# Power_Sense_Rev_2_2_1.net
KiCad netlist of a schematic drawn in EAGLE
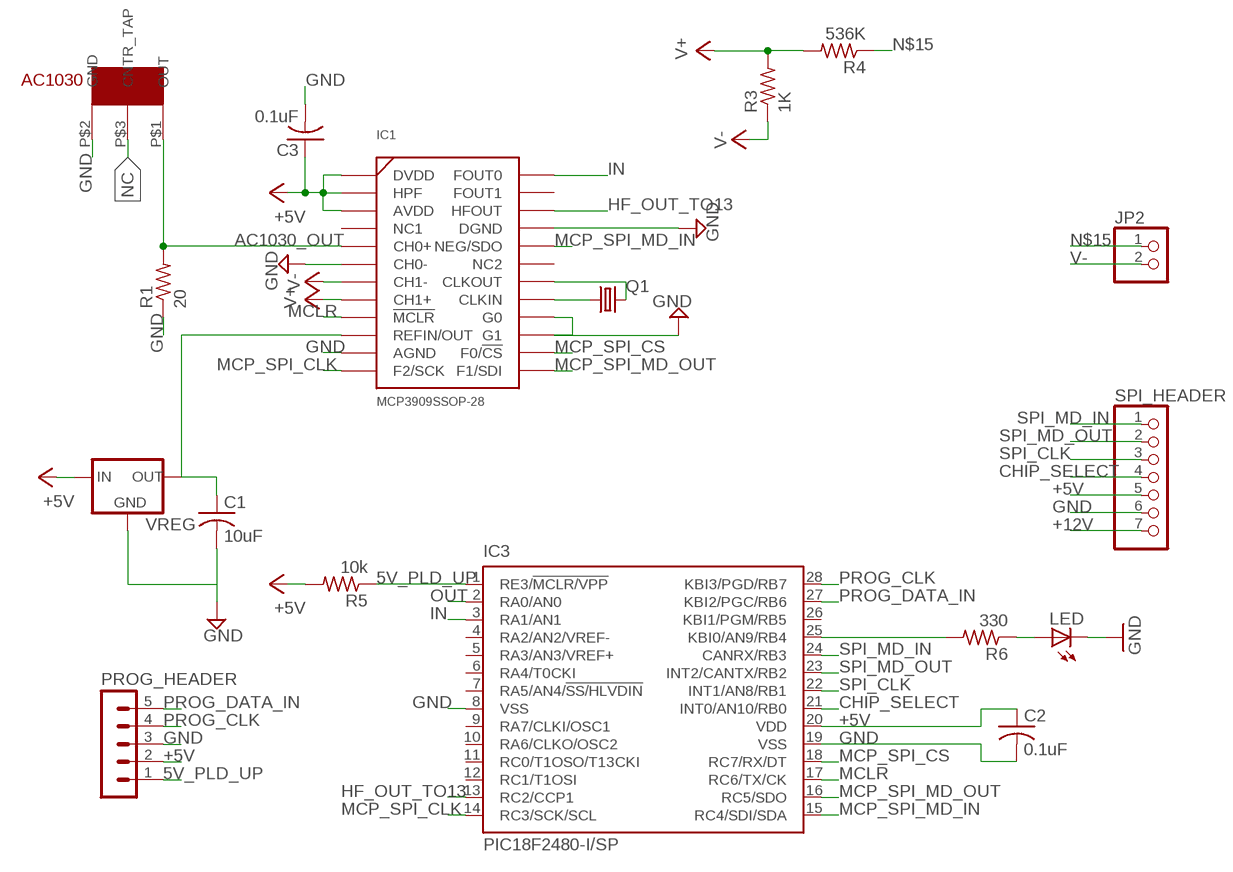
[diagram p0: schematic, sheet 1]

(export (version "E")
  (design (tool "Eeschema 10.0.6"))
  (components
    (comp (ref "AC1030")
      (value "AC1030")
      (footprint "eagle-import:AC1030")
      (libsource (lib "eagle-import") (part "AC1030"))
    )
    (comp (ref "C1")
      (value "10uF")
      (footprint "eagle-import:C025-024X044")
      (libsource (lib "eagle-import") (part "C-US025-024X044"))
    )
    (comp (ref "C2")
      (value "0.1uF")
      (footprint "eagle-import:C025-024X044")
      (libsource (lib "eagle-import") (part "C-US025-024X044"))
    )
    (comp (ref "C3")
      (value "0.1uF")
      (footprint "eagle-import:C025-024X044")
      (libsource (lib "eagle-import") (part "C-US025-024X044"))
    )
    (comp (ref "IC1")
      (value "MCP3909SSOP-28")
      (footprint "eagle-import:SSOP-24")
      (libsource (lib "eagle-import") (part "MCP3909SSOP-28"))
    )
    (comp (ref "IC3")
      (value "PIC18F2480-I/SP")
      (footprint "eagle-import:DIL28-3")
      (fields (field (name "MF") "MICROCHIP"))
      (libsource (lib "eagle-import") (part "PIC18F280-I/SP4"))
    )
    (comp (ref "JP2")
      (value "PINHD-1X2")
      (footprint "eagle-import:1X02")
      (libsource (lib "eagle-import") (part "PINHD-1X2"))
    )
    (comp (ref "LED")
      (value "LED3MM")
      (footprint "eagle-import:LED3MM")
      (libsource (lib "eagle-import") (part "LED3MM"))
    )
    (comp (ref "PROG_HEADER")
      (value "MA05-1")
      (footprint "eagle-import:MA05-1")
      (libsource (lib "eagle-import") (part "MA05-1"))
    )
    (comp (ref "Q1")
      (value "CRYSTALHC49S")
      (footprint "eagle-import:HC49_S")
      (libsource (lib "eagle-import") (part "CRYSTALHC49S"))
    )
    (comp (ref "R1")
      (value "20")
      (footprint "eagle-import:0204_7")
      (libsource (lib "eagle-import") (part "R-US_0204/7"))
    )
    (comp (ref "R3")
      (value "1K")
      (footprint "eagle-import:0204_7")
      (libsource (lib "eagle-import") (part "R-US_0204/7"))
    )
    (comp (ref "R4")
      (value "536K")
      (footprint "eagle-import:0204_7")
      (libsource (lib "eagle-import") (part "R-US_0204/7"))
    )
    (comp (ref "R5")
      (value "10k")
      (footprint "eagle-import:0204_7")
      (libsource (lib "eagle-import") (part "R-US_0204/7"))
    )
    (comp (ref "R6")
      (value "330")
      (footprint "eagle-import:0204_7")
      (libsource (lib "eagle-import") (part "R-US_0204/7"))
    )
    (comp (ref "SPI_HEADER")
      (value "PINHD-1X7")
      (footprint "eagle-import:1X07")
      (libsource (lib "eagle-import") (part "PINHD-1X7"))
    )
    (comp (ref "VREG")
      (value "MCP1700INLINE")
      (footprint "eagle-import:TO92-INLINE")
      (libsource (lib "eagle-import") (part "MCP1700INLINE"))
    )
  )
  (nets
    (net (code "1") (name "+5V") (class "Default")
      (node (ref "C2") (pin "1") (pinfunction "1_1") (pintype "passive"))
      (node (ref "C3") (pin "1") (pinfunction "1_1") (pintype "passive"))
      (node (ref "IC1") (pin "1") (pinfunction "DVDD_1") (pintype "bidirectional"))
      (node (ref "IC1") (pin "2") (pinfunction "HPF_2") (pintype "bidirectional"))
      (node (ref "IC1") (pin "3") (pinfunction "AVDD_3") (pintype "bidirectional"))
      (node (ref "IC3") (pin "20") (pinfunction "VDD_20") (pintype "power_in"))
      (node (ref "PROG_HEADER") (pin "2") (pinfunction "2_2") (pintype "passive"))
      (node (ref "R5") (pin "2") (pinfunction "2_2") (pintype "passive"))
      (node (ref "SPI_HEADER") (pin "5") (pinfunction "5_5") (pintype "passive"))
      (node (ref "VREG") (pin "2") (pinfunction "IN_2") (pintype "input"))
    )
    (net (code "2") (name "/+12V") (class "Default")
      (node (ref "SPI_HEADER") (pin "7") (pinfunction "7_7") (pintype "passive"))
    )
    (net (code "3") (name "/5V_PLD_UP") (class "Default")
      (node (ref "IC3") (pin "1") (pinfunction "RE3/~{MCLR/VPP}_1") (pintype "input"))
      (node (ref "PROG_HEADER") (pin "1") (pinfunction "1_1") (pintype "passive"))
      (node (ref "R5") (pin "1") (pinfunction "1_1") (pintype "passive"))
    )
    (net (code "4") (name "/AC1030_OUT") (class "Default")
      (node (ref "AC1030") (pin "P$1") (pinfunction "OUT_P$1") (pintype "output"))
      (node (ref "IC1") (pin "5") (pinfunction "CH0+_5") (pintype "bidirectional"))
      (node (ref "R1") (pin "2") (pinfunction "2_2") (pintype "passive"))
    )
    (net (code "5") (name "/CHIP_SELECT") (class "Default")
      (node (ref "IC3") (pin "21") (pinfunction "INT0/AN10/RB0_21") (pintype "bidirectional"))
      (node (ref "SPI_HEADER") (pin "4") (pinfunction "4_4") (pintype "passive"))
    )
    (net (code "6") (name "/HF_OUT_TO13") (class "Default")
      (node (ref "IC1") (pin "22") (pinfunction "HFOUT_22") (pintype "bidirectional"))
      (node (ref "IC3") (pin "13") (pinfunction "RC2/CCP1_13") (pintype "bidirectional"))
    )
    (net (code "7") (name "/IN") (class "Default")
      (node (ref "IC1") (pin "24") (pinfunction "FOUT0_24") (pintype "bidirectional"))
      (node (ref "IC3") (pin "3") (pinfunction "RA1/AN1_3") (pintype "bidirectional"))
    )
    (net (code "8") (name "/MCLR") (class "Default")
      (node (ref "IC1") (pin "9") (pinfunction "~{MCLR}_9") (pintype "bidirectional"))
      (node (ref "IC3") (pin "17") (pinfunction "RC6/TX/CK_17") (pintype "bidirectional"))
    )
    (net (code "9") (name "/MCP_SPI_CLK") (class "Default")
      (node (ref "IC1") (pin "12") (pinfunction "F2/SCK_12") (pintype "bidirectional"))
      (node (ref "IC3") (pin "14") (pinfunction "RC3/SCK/SCL_14") (pintype "bidirectional"))
    )
    (net (code "10") (name "/MCP_SPI_CS") (class "Default")
      (node (ref "IC1") (pin "14") (pinfunction "F0/~{CS}_14") (pintype "bidirectional"))
      (node (ref "IC3") (pin "18") (pinfunction "RC7/RX/DT_18") (pintype "bidirectional"))
    )
    (net (code "11") (name "/MCP_SPI_MD_IN") (class "Default")
      (node (ref "IC1") (pin "20") (pinfunction "NEG/SDO_20") (pintype "bidirectional"))
      (node (ref "IC3") (pin "15") (pinfunction "RC4/SDI/SDA_15") (pintype "bidirectional"))
    )
    (net (code "12") (name "/MCP_SPI_MD_OUT") (class "Default")
      (node (ref "IC1") (pin "13") (pinfunction "F1/SDI_13") (pintype "bidirectional"))
      (node (ref "IC3") (pin "16") (pinfunction "RC5/SDO_16") (pintype "bidirectional"))
    )
    (net (code "13") (name "/N$15") (class "Default")
      (node (ref "JP2") (pin "1") (pinfunction "1_1") (pintype "passive"))
      (node (ref "R4") (pin "1") (pinfunction "1_1") (pintype "passive"))
    )
    (net (code "14") (name "/OUT") (class "Default")
      (node (ref "IC3") (pin "2") (pinfunction "RA0/AN0_2") (pintype "bidirectional"))
    )
    (net (code "15") (name "/PROG_CLK") (class "Default")
      (node (ref "IC3") (pin "28") (pinfunction "KBI3/PGD/RB7_28") (pintype "bidirectional"))
      (node (ref "PROG_HEADER") (pin "4") (pinfunction "4_4") (pintype "passive"))
    )
    (net (code "16") (name "/PROG_DATA_IN") (class "Default")
      (node (ref "IC3") (pin "27") (pinfunction "KBI2/PGC/RB6_27") (pintype "bidirectional"))
      (node (ref "PROG_HEADER") (pin "5") (pinfunction "5_5") (pintype "passive"))
    )
    (net (code "17") (name "/SPI_CLK") (class "Default")
      (node (ref "IC3") (pin "22") (pinfunction "INT1/AN8/RB1_22") (pintype "bidirectional"))
      (node (ref "SPI_HEADER") (pin "3") (pinfunction "3_3") (pintype "passive"))
    )
    (net (code "18") (name "/SPI_MD_IN") (class "Default")
      (node (ref "IC3") (pin "24") (pinfunction "CANRX/RB3_24") (pintype "bidirectional"))
      (node (ref "SPI_HEADER") (pin "1") (pinfunction "1_1") (pintype "passive"))
    )
    (net (code "19") (name "/SPI_MD_OUT") (class "Default")
      (node (ref "IC3") (pin "23") (pinfunction "INT2/CANTX/RB2_23") (pintype "bidirectional"))
      (node (ref "SPI_HEADER") (pin "2") (pinfunction "2_2") (pintype "passive"))
    )
    (net (code "20") (name "GND") (class "Default")
      (node (ref "AC1030") (pin "P$2") (pinfunction "GND_P$2") (pintype "output"))
      (node (ref "C1") (pin "2") (pinfunction "2_2") (pintype "passive"))
      (node (ref "C2") (pin "2") (pinfunction "2_2") (pintype "passive"))
      (node (ref "C3") (pin "2") (pinfunction "2_2") (pintype "passive"))
      (node (ref "IC1") (pin "11") (pinfunction "AGND_11") (pintype "bidirectional"))
      (node (ref "IC1") (pin "15") (pinfunction "G1_15") (pintype "bidirectional"))
      (node (ref "IC1") (pin "16") (pinfunction "G0_16") (pintype "bidirectional"))
      (node (ref "IC1") (pin "21") (pinfunction "DGND_21") (pintype "bidirectional"))
      (node (ref "IC1") (pin "6") (pinfunction "CH0-_6") (pintype "bidirectional"))
      (node (ref "IC3") (pin "19") (pinfunction "VSS_19") (pintype "power_in"))
      (node (ref "IC3") (pin "8") (pinfunction "VSS_8") (pintype "power_in"))
      (node (ref "LED") (pin "K") (pinfunction "C_K") (pintype "passive"))
      (node (ref "PROG_HEADER") (pin "3") (pinfunction "3_3") (pintype "passive"))
      (node (ref "R1") (pin "1") (pinfunction "1_1") (pintype "passive"))
      (node (ref "SPI_HEADER") (pin "6") (pinfunction "6_6") (pintype "passive"))
      (node (ref "VREG") (pin "1") (pinfunction "GND_1") (pintype "input"))
    )
    (net (code "21") (name "NC") (class "Default")
      (node (ref "AC1030") (pin "P$3") (pinfunction "CNTR_TAP_P$3") (pintype "output"))
    )
    (net (code "22") (name "Net-(IC1-CLKIN)") (class "Default")
      (node (ref "IC1") (pin "17") (pinfunction "CLKIN_17") (pintype "bidirectional"))
      (node (ref "Q1") (pin "1") (pinfunction "1_1") (pintype "passive"))
    )
    (net (code "23") (name "Net-(IC1-CLKOUT)") (class "Default")
      (node (ref "IC1") (pin "18") (pinfunction "CLKOUT_18") (pintype "bidirectional"))
      (node (ref "Q1") (pin "2") (pinfunction "2_2") (pintype "passive"))
    )
    (net (code "24") (name "Net-(IC1-REFIN{slash}OUT)") (class "Default")
      (node (ref "C1") (pin "1") (pinfunction "1_1") (pintype "passive"))
      (node (ref "IC1") (pin "10") (pinfunction "REFIN/OUT_10") (pintype "bidirectional"))
      (node (ref "VREG") (pin "3") (pinfunction "OUT_3") (pintype "passive"))
    )
    (net (code "25") (name "Net-(IC3-KBI0{slash}AN9{slash}RB4)") (class "Default")
      (node (ref "IC3") (pin "25") (pinfunction "KBI0/AN9/RB4_25") (pintype "bidirectional"))
      (node (ref "R6") (pin "2") (pinfunction "2_2") (pintype "passive"))
    )
    (net (code "26") (name "Net-(LED-PadA)") (class "Default")
      (node (ref "LED") (pin "A") (pinfunction "A_A") (pintype "passive"))
      (node (ref "R6") (pin "1") (pinfunction "1_1") (pintype "passive"))
    )
    (net (code "27") (name "V+") (class "Default")
      (node (ref "IC1") (pin "8") (pinfunction "CH1+_8") (pintype "bidirectional"))
      (node (ref "R3") (pin "2") (pinfunction "2_2") (pintype "passive"))
      (node (ref "R4") (pin "2") (pinfunction "2_2") (pintype "passive"))
    )
    (net (code "28") (name "V-") (class "Default")
      (node (ref "IC1") (pin "7") (pinfunction "CH1-_7") (pintype "bidirectional"))
      (node (ref "JP2") (pin "2") (pinfunction "2_2") (pintype "passive"))
      (node (ref "R3") (pin "1") (pinfunction "1_1") (pintype "passive"))
    )
    (net (code "29") (name "unconnected-(IC1-FOUT1-Pad23)") (class "Default")
      (node (ref "IC1") (pin "23") (pinfunction "FOUT1_23") (pintype "bidirectional"))
    )
    (net (code "30") (name "unconnected-(IC1-NC1-Pad4)") (class "Default")
      (node (ref "IC1") (pin "4") (pinfunction "NC1_4") (pintype "bidirectional"))
    )
    (net (code "31") (name "unconnected-(IC1-NC2-Pad19)") (class "Default")
      (node (ref "IC1") (pin "19") (pinfunction "NC2_19") (pintype "bidirectional"))
    )
    (net (code "32") (name "unconnected-(IC3-KBI1{slash}PGM{slash}RB5-Pad26)") (class "Default")
      (node (ref "IC3") (pin "26") (pinfunction "KBI1/PGM/RB5_26") (pintype "bidirectional"))
    )
    (net (code "33") (name "unconnected-(IC3-RA2{slash}AN2{slash}VREF--Pad4)") (class "Default")
      (node (ref "IC3") (pin "4") (pinfunction "RA2/AN2/VREF-_4") (pintype "bidirectional"))
    )
    (net (code "34") (name "unconnected-(IC3-RA3{slash}AN3{slash}VREF+-Pad5)") (class "Default")
      (node (ref "IC3") (pin "5") (pinfunction "RA3/AN3/VREF+_5") (pintype "bidirectional"))
    )
    (net (code "35") (name "unconnected-(IC3-RA4{slash}T0CKI-Pad6)") (class "Default")
      (node (ref "IC3") (pin "6") (pinfunction "RA4/T0CKI_6") (pintype "bidirectional"))
    )
    (net (code "36") (name "unconnected-(IC3-RA5{slash}AN4{slash}~{SS{slash}HLVDIN}-Pad7)") (class "Default")
      (node (ref "IC3") (pin "7") (pinfunction "RA5/AN4/~{SS/HLVDIN}_7") (pintype "bidirectional"))
    )
    (net (code "37") (name "unconnected-(IC3-RA6{slash}CLKO{slash}OSC2-Pad10)") (class "Default")
      (node (ref "IC3") (pin "10") (pinfunction "RA6/CLKO/OSC2_10") (pintype "output"))
    )
    (net (code "38") (name "unconnected-(IC3-RA7{slash}CLKI{slash}OSC1-Pad9)") (class "Default")
      (node (ref "IC3") (pin "9") (pinfunction "RA7/CLKI/OSC1_9") (pintype "input"))
    )
    (net (code "39") (name "unconnected-(IC3-RC0{slash}T1OSO{slash}T13CKI-Pad11)") (class "Default")
      (node (ref "IC3") (pin "11") (pinfunction "RC0/T1OSO/T13CKI_11") (pintype "bidirectional"))
    )
    (net (code "40") (name "unconnected-(IC3-RC1{slash}T1OSI-Pad12)") (class "Default")
      (node (ref "IC3") (pin "12") (pinfunction "RC1/T1OSI_12") (pintype "bidirectional"))
    )
  )
)
